# CATS-Vega-Radio.net
KiCad netlist of a schematic drawn in Altium Designer
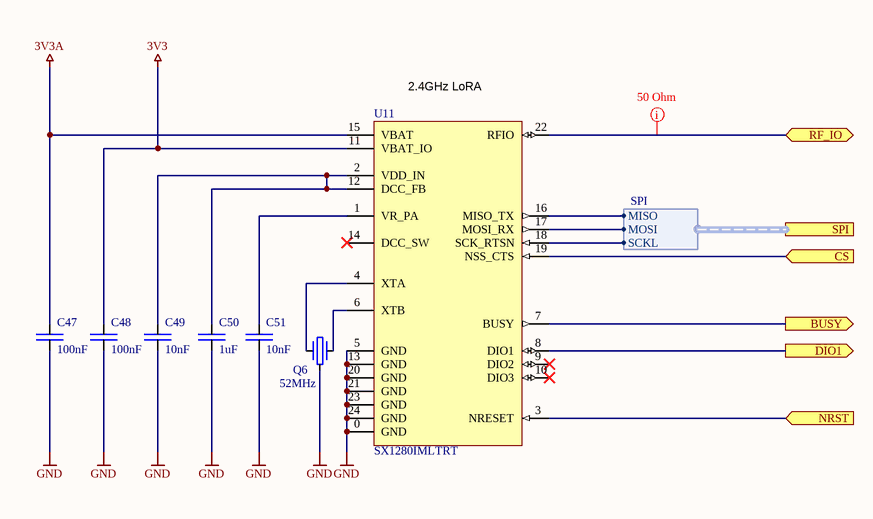
[diagram p0: CATS-Vega-Radio.SchDoc]

(export (version "E")
  (design (tool "Eeschema 10.0.6"))
  (components
    (comp (ref "C47")
      (value "100nF")
      (footprint "SMD Keramikkondensator 0603")
      (description "SMD Ceramic Capacitor E6")
      (libsource (lib "CATS-EUROC") (part "E6 - 100nF"))
    )
    (comp (ref "C48")
      (value "100nF")
      (footprint "SMD Keramikkondensator 0603")
      (description "SMD Ceramic Capacitor E6")
      (libsource (lib "CATS-EUROC") (part "E6 - 100nF"))
    )
    (comp (ref "C49")
      (value "10nF")
      (footprint "SMD Keramikkondensator 0603")
      (description "SMD Ceramic Capacitor E6")
      (libsource (lib "CATS-EUROC") (part "E6 - 10nF"))
    )
    (comp (ref "C50")
      (value "1uF")
      (footprint "SMD Keramikkondensator 0603")
      (description "SMD Ceramic Capacitor E6")
      (libsource (lib "CATS-EUROC") (part "E6 - 1uF"))
    )
    (comp (ref "C51")
      (value "10nF")
      (footprint "SMD Keramikkondensator 0603")
      (description "SMD Ceramic Capacitor E6")
      (libsource (lib "CATS-EUROC") (part "E6 - 10nF"))
    )
    (comp (ref "Q6")
      (value "52MHz")
      (footprint "SMD Crystal 2520")
      (description "52Mhz Ceramic 2.5 x 2.0mm SMD 10pF 60Ω ±10ppm")
      (libsource (lib "Other") (part "Crystal 52MHz - 2520"))
    )
    (comp (ref "U11")
      (value "SX1280IMLTRT")
      (footprint "SMD IC QFN-24")
      (description "Long Range, Low Power, 2.4 GHz\r\nTransceiver with Ranging Capability")
      (libsource (lib "RF") (part "SX1280IMLTRT"))
    )
  )
  (nets
    (net (code "2") (name "/BUSY") (class "Default")
      (node (ref "U11") (pin "7") (pinfunction "BUSY_7") (pintype "output"))
    )
    (net (code "3") (name "/CS") (class "Default")
      (node (ref "U11") (pin "19") (pinfunction "NSS_CTS_19") (pintype "input"))
    )
    (net (code "4") (name "/DIO1") (class "Default")
      (node (ref "U11") (pin "8") (pinfunction "DIO1_8") (pintype "bidirectional"))
    )
    (net (code "5") (name "/MISO") (class "Default")
      (node (ref "U11") (pin "16") (pinfunction "MISO_TX_16") (pintype "output"))
    )
    (net (code "6") (name "/MOSI") (class "Default")
      (node (ref "U11") (pin "17") (pinfunction "MOSI_RX_17") (pintype "output"))
    )
    (net (code "7") (name "/NRST") (class "Default")
      (node (ref "U11") (pin "3") (pinfunction "NRESET_3") (pintype "input"))
    )
    (net (code "8") (name "/RF_IO") (class "Default")
      (node (ref "U11") (pin "22") (pinfunction "RFIO_22") (pintype "bidirectional"))
    )
    (net (code "9") (name "/SCKL") (class "Default")
      (node (ref "U11") (pin "18") (pinfunction "SCK_RTSN_18") (pintype "input"))
    )
    (net (code "11") (name "3V3") (class "Default")
      (node (ref "C48") (pin "2") (pinfunction "2_2") (pintype "passive"))
      (node (ref "U11") (pin "11") (pinfunction "VBAT_IO_11") (pintype "passive"))
    )
    (net (code "12") (name "3V3A") (class "Default")
      (node (ref "C47") (pin "2") (pinfunction "2_2") (pintype "passive"))
      (node (ref "U11") (pin "15") (pinfunction "VBAT_15") (pintype "passive"))
    )
    (net (code "13") (name "GND") (class "Default")
      (node (ref "C47") (pin "1") (pinfunction "1_1") (pintype "passive"))
      (node (ref "C48") (pin "1") (pinfunction "1_1") (pintype "passive"))
      (node (ref "C49") (pin "1") (pinfunction "1_1") (pintype "passive"))
      (node (ref "C50") (pin "1") (pinfunction "1_1") (pintype "passive"))
      (node (ref "C51") (pin "1") (pinfunction "1_1") (pintype "passive"))
      (node (ref "Q6") (pin "3") (pinfunction "3_3") (pintype "power_in"))
      (node (ref "U11") (pin "0") (pinfunction "GND_0") (pintype "passive"))
      (node (ref "U11") (pin "13") (pinfunction "GND_13") (pintype "passive"))
      (node (ref "U11") (pin "20") (pinfunction "GND_20") (pintype "passive"))
      (node (ref "U11") (pin "21") (pinfunction "GND_21") (pintype "passive"))
      (node (ref "U11") (pin "23") (pinfunction "GND_23") (pintype "passive"))
      (node (ref "U11") (pin "24") (pinfunction "GND_24") (pintype "passive"))
      (node (ref "U11") (pin "5") (pinfunction "GND_5") (pintype "passive"))
    )
    (net (code "14") (name "Net-(U11-DCC_FB)") (class "Default")
      (node (ref "C49") (pin "2") (pinfunction "2_2") (pintype "passive"))
      (node (ref "C50") (pin "2") (pinfunction "2_2") (pintype "passive"))
      (node (ref "U11") (pin "12") (pinfunction "DCC_FB_12") (pintype "passive"))
      (node (ref "U11") (pin "2") (pinfunction "VDD_IN_2") (pintype "passive"))
    )
    (net (code "15") (name "Net-(U11-VR_PA)") (class "Default")
      (node (ref "C51") (pin "2") (pinfunction "2_2") (pintype "passive"))
      (node (ref "U11") (pin "1") (pinfunction "VR_PA_1") (pintype "passive"))
    )
    (net (code "16") (name "Net-(U11-XTA)") (class "Default")
      (node (ref "Q6") (pin "1") (pinfunction "1_1") (pintype "passive"))
      (node (ref "U11") (pin "4") (pinfunction "XTA_4") (pintype "passive"))
    )
    (net (code "17") (name "Net-(U11-XTB)") (class "Default")
      (node (ref "Q6") (pin "2") (pinfunction "2_2") (pintype "passive"))
      (node (ref "U11") (pin "6") (pinfunction "XTB_6") (pintype "passive"))
    )
    (net (code "18") (name "unconnected-(U11-DCC_SW-Pad14)") (class "Default")
      (node (ref "U11") (pin "14") (pinfunction "DCC_SW_14") (pintype "passive+no_connect"))
    )
    (net (code "19") (name "unconnected-(U11-DIO2-Pad9)") (class "Default")
      (node (ref "U11") (pin "9") (pinfunction "DIO2_9") (pintype "bidirectional+no_connect"))
    )
    (net (code "20") (name "unconnected-(U11-DIO3-Pad10)") (class "Default")
      (node (ref "U11") (pin "10") (pinfunction "DIO3_10") (pintype "bidirectional+no_connect"))
    )
  )
)
